# esquema.net
KiCad netlist of a schematic drawn in EAGLE
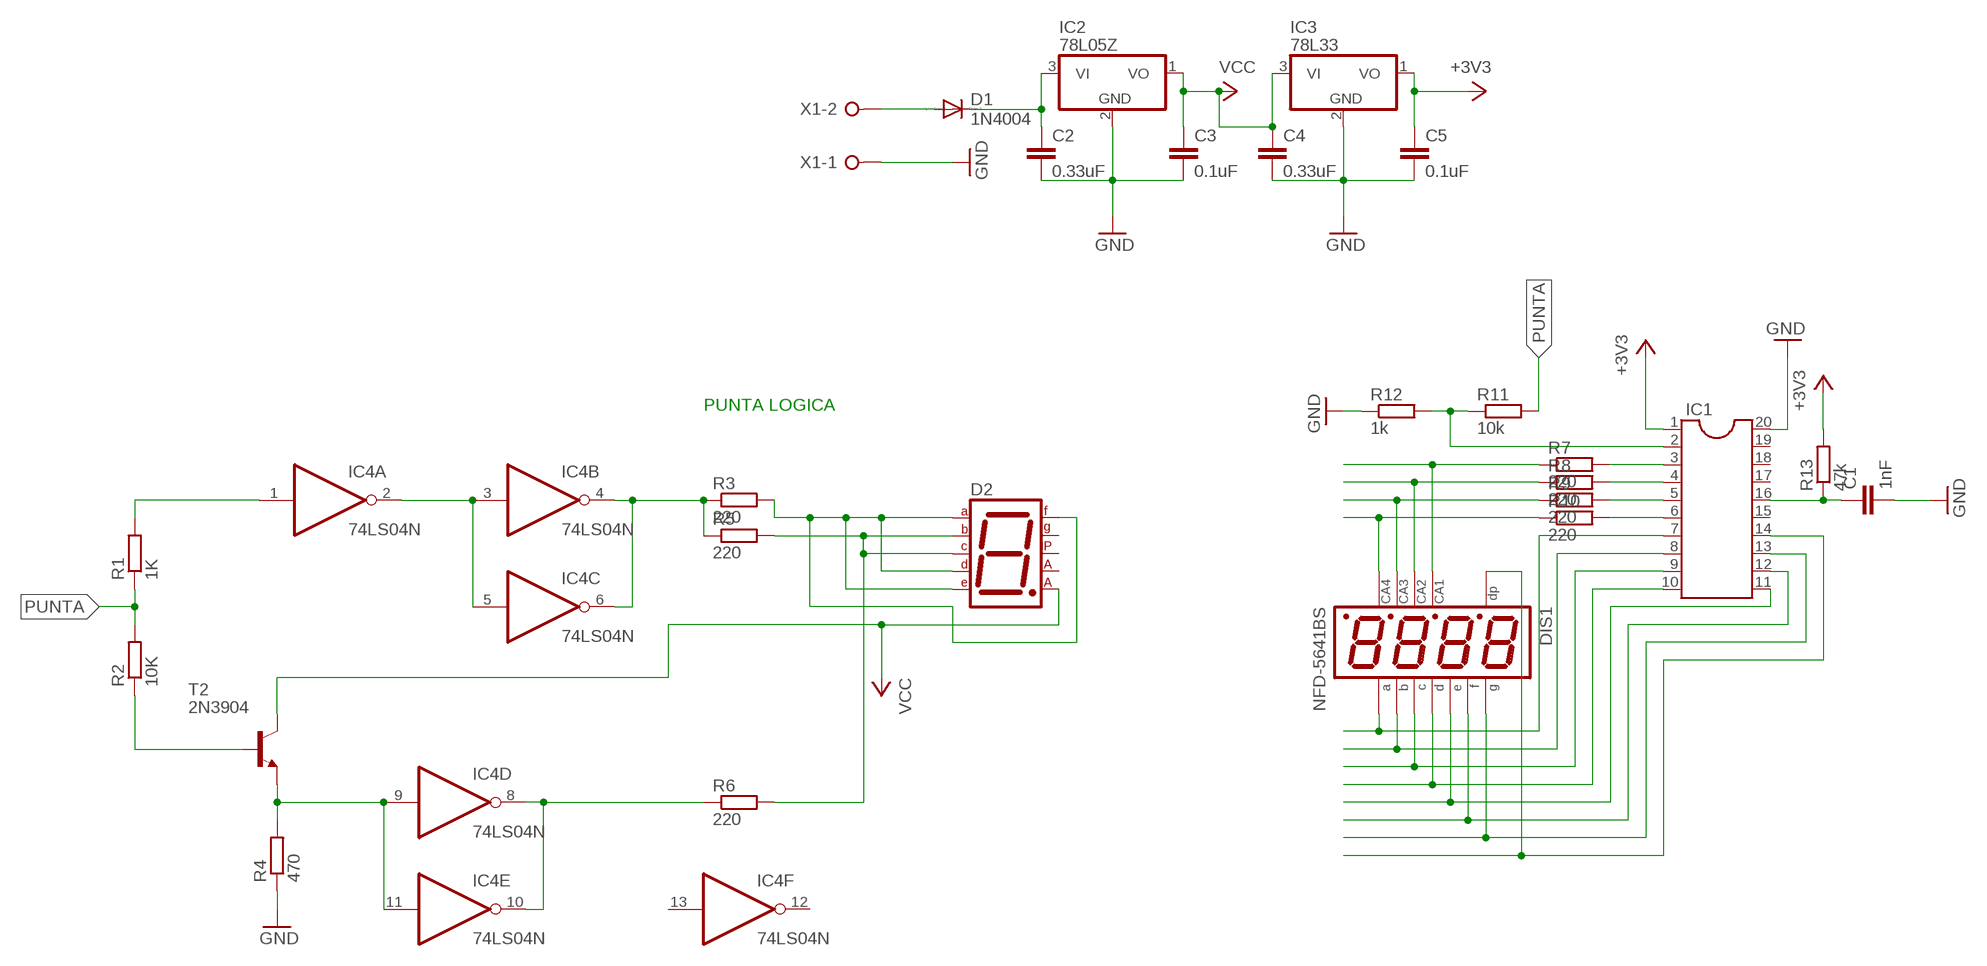
[diagram p0: schematic, sheet 1]

(export (version "E")
  (design (tool "Eeschema 10.0.6"))
  (components
    (comp (ref "C1")
      (value "1nF")
      (footprint "eagle-import:C050-024X044")
      (libsource (lib "eagle-import") (part "C-EU050-024X044"))
    )
    (comp (ref "C2")
      (value "0.33uF")
      (footprint "eagle-import:C050-024X044")
      (libsource (lib "eagle-import") (part "C-EU050-024X044"))
    )
    (comp (ref "C3")
      (value "0.1uF")
      (footprint "eagle-import:C050-024X044")
      (libsource (lib "eagle-import") (part "C-EU050-024X044"))
    )
    (comp (ref "C4")
      (value "0.33uF")
      (footprint "eagle-import:C050-024X044")
      (libsource (lib "eagle-import") (part "C-EU050-024X044"))
    )
    (comp (ref "C5")
      (value "0.1uF")
      (footprint "eagle-import:C050-024X044")
      (libsource (lib "eagle-import") (part "C-EU050-024X044"))
    )
    (comp (ref "D1")
      (value "1N4004")
      (footprint "eagle-import:DO41-10")
      (libsource (lib "eagle-import") (part "1N4004"))
    )
    (comp (ref "D2")
      (value "7SEG-CA")
      (footprint "eagle-import:7SEG-13")
      (libsource (lib "eagle-import") (part "7SEG-CA"))
    )
    (comp (ref "DIS1")
      (value "NFD-5641BS")
      (footprint "eagle-import:NFD-5641")
      (libsource (lib "eagle-import") (part "NFD-5641BS"))
    )
    (comp (ref "IC1")
      (value "DIL20S")
      (footprint "eagle-import:SOCKET-20")
      (libsource (lib "eagle-import") (part "DIL20S"))
    )
    (comp (ref "IC2")
      (value "78L05Z")
      (footprint "eagle-import:TO92")
      (libsource (lib "eagle-import") (part "78ZL05"))
    )
    (comp (ref "IC3")
      (value "78L33")
      (footprint "eagle-import:TO92")
      (libsource (lib "eagle-import") (part "78ZL05"))
    )
    (comp (ref "IC4")
      (value "74LS04N")
      (footprint "eagle-import:DIL14")
      (libsource (lib "eagle-import") (part "7404NLS"))
    )
    (comp (ref "R1")
      (value "1K")
      (footprint "eagle-import:0207_7")
      (libsource (lib "eagle-import") (part "R-EU_0207/7"))
    )
    (comp (ref "R2")
      (value "10K")
      (footprint "eagle-import:0207_7")
      (libsource (lib "eagle-import") (part "R-EU_0207/7"))
    )
    (comp (ref "R3")
      (value "220")
      (footprint "eagle-import:0207_7")
      (libsource (lib "eagle-import") (part "R-EU_0207/7"))
    )
    (comp (ref "R4")
      (value "470")
      (footprint "eagle-import:0207_7")
      (libsource (lib "eagle-import") (part "R-EU_0207/7"))
    )
    (comp (ref "R5")
      (value "220")
      (footprint "eagle-import:0207_7")
      (libsource (lib "eagle-import") (part "R-EU_0207/7"))
    )
    (comp (ref "R6")
      (value "220")
      (footprint "eagle-import:0207_7")
      (libsource (lib "eagle-import") (part "R-EU_0207/7"))
    )
    (comp (ref "R7")
      (value "220")
      (footprint "eagle-import:0207_7")
      (libsource (lib "eagle-import") (part "R-EU_0207/7"))
    )
    (comp (ref "R8")
      (value "220")
      (footprint "eagle-import:0207_7")
      (libsource (lib "eagle-import") (part "R-EU_0207/7"))
    )
    (comp (ref "R9")
      (value "220")
      (footprint "eagle-import:0207_7")
      (libsource (lib "eagle-import") (part "R-EU_0207/7"))
    )
    (comp (ref "R10")
      (value "220")
      (footprint "eagle-import:0207_7")
      (libsource (lib "eagle-import") (part "R-EU_0207/7"))
    )
    (comp (ref "R11")
      (value "10k")
      (footprint "eagle-import:0207_7")
      (libsource (lib "eagle-import") (part "R-EU_0207/7"))
    )
    (comp (ref "R12")
      (value "1k")
      (footprint "eagle-import:0207_7")
      (libsource (lib "eagle-import") (part "R-EU_0207/7"))
    )
    (comp (ref "R13")
      (value "47k")
      (footprint "eagle-import:0207_7")
      (libsource (lib "eagle-import") (part "R-EU_0207/7"))
    )
    (comp (ref "T2")
      (value "2N3904")
      (footprint "eagle-import:TO92")
      (libsource (lib "eagle-import") (part "2N3904"))
    )
    (comp (ref "X1")
      (value "W237-02P")
      (footprint "eagle-import:W237-132")
      (libsource (lib "eagle-import") (part "W237-02P"))
    )
  )
  (nets
    (net (code "1") (name "+3V3") (class "Default")
      (node (ref "C5") (pin "1") (pinfunction "1_1") (pintype "passive"))
      (node (ref "IC1") (pin "1") (pinfunction "1_1") (pintype "passive"))
      (node (ref "IC3") (pin "1") (pinfunction "VO_1") (pintype "passive"))
      (node (ref "R13") (pin "2") (pinfunction "2_2") (pintype "passive"))
    )
    (net (code "2") (name "GND") (class "Default")
      (node (ref "C1") (pin "2") (pinfunction "2_2") (pintype "passive"))
      (node (ref "C2") (pin "2") (pinfunction "2_2") (pintype "passive"))
      (node (ref "C3") (pin "2") (pinfunction "2_2") (pintype "passive"))
      (node (ref "C4") (pin "2") (pinfunction "2_2") (pintype "passive"))
      (node (ref "C5") (pin "2") (pinfunction "2_2") (pintype "passive"))
      (node (ref "IC1") (pin "20") (pinfunction "20_20") (pintype "passive"))
      (node (ref "IC2") (pin "2") (pinfunction "GND_2") (pintype "passive"))
      (node (ref "IC3") (pin "2") (pinfunction "GND_2") (pintype "passive"))
      (node (ref "R12") (pin "1") (pinfunction "1_1") (pintype "passive"))
      (node (ref "R4") (pin "1") (pinfunction "1_1") (pintype "passive"))
      (node (ref "X1") (pin "1") (pinfunction "KL_1") (pintype "passive"))
    )
    (net (code "3") (name "Net-(C1-Pad1)") (class "Default")
      (node (ref "C1") (pin "1") (pinfunction "1_1") (pintype "passive"))
      (node (ref "IC1") (pin "16") (pinfunction "16_16") (pintype "passive"))
      (node (ref "R13") (pin "1") (pinfunction "1_1") (pintype "passive"))
    )
    (net (code "4") (name "Net-(D2-A)") (class "Default")
      (node (ref "D2") (pin "1") (pinfunction "E_1") (pintype "passive"))
      (node (ref "D2") (pin "2") (pinfunction "D_2") (pintype "passive"))
      (node (ref "D2") (pin "7") (pinfunction "A_7") (pintype "passive"))
      (node (ref "D2") (pin "9") (pinfunction "F_9") (pintype "passive"))
      (node (ref "R3") (pin "2") (pinfunction "2_2") (pintype "passive"))
    )
    (net (code "5") (name "Net-(D2-B)") (class "Default")
      (node (ref "D2") (pin "4") (pinfunction "C_4") (pintype "passive"))
      (node (ref "D2") (pin "6") (pinfunction "B_6") (pintype "passive"))
      (node (ref "R5") (pin "2") (pinfunction "2_2") (pintype "passive"))
      (node (ref "R6") (pin "2") (pinfunction "2_2") (pintype "passive"))
    )
    (net (code "6") (name "Net-(DIS1-PadP$1)") (class "Default")
      (node (ref "DIS1") (pin "P$1") (pinfunction "P$1_P$1") (pintype "bidirectional"))
      (node (ref "IC1") (pin "11") (pinfunction "11_11") (pintype "passive"))
    )
    (net (code "7") (name "Net-(DIS1-PadP$2)") (class "Default")
      (node (ref "DIS1") (pin "P$2") (pinfunction "P$2_P$2") (pintype "bidirectional"))
      (node (ref "IC1") (pin "10") (pinfunction "10_10") (pintype "passive"))
    )
    (net (code "8") (name "Net-(DIS1-PadP$3)") (class "Default")
      (node (ref "DIS1") (pin "P$3") (pinfunction "P$3_P$3") (pintype "bidirectional"))
      (node (ref "IC1") (pin "14") (pinfunction "14_14") (pintype "passive"))
    )
    (net (code "9") (name "Net-(DIS1-PadP$4)") (class "Default")
      (node (ref "DIS1") (pin "P$4") (pinfunction "P$4_P$4") (pintype "bidirectional"))
      (node (ref "IC1") (pin "9") (pinfunction "9_9") (pintype "passive"))
    )
    (net (code "10") (name "Net-(DIS1-PadP$5)") (class "Default")
      (node (ref "DIS1") (pin "P$5") (pinfunction "P$5_P$5") (pintype "bidirectional"))
      (node (ref "IC1") (pin "13") (pinfunction "13_13") (pintype "passive"))
    )
    (net (code "11") (name "Net-(DIS1-PadP$6)") (class "Default")
      (node (ref "DIS1") (pin "P$6") (pinfunction "P$6_P$6") (pintype "bidirectional"))
      (node (ref "R10") (pin "1") (pinfunction "1_1") (pintype "passive"))
    )
    (net (code "12") (name "Net-(DIS1-PadP$7)") (class "Default")
      (node (ref "DIS1") (pin "P$7") (pinfunction "P$7_P$7") (pintype "bidirectional"))
      (node (ref "IC1") (pin "8") (pinfunction "8_8") (pintype "passive"))
    )
    (net (code "13") (name "Net-(DIS1-PadP$8)") (class "Default")
      (node (ref "DIS1") (pin "P$8") (pinfunction "P$8_P$8") (pintype "bidirectional"))
      (node (ref "R9") (pin "1") (pinfunction "1_1") (pintype "passive"))
    )
    (net (code "14") (name "Net-(DIS1-PadP$9)") (class "Default")
      (node (ref "DIS1") (pin "P$9") (pinfunction "P$9_P$9") (pintype "bidirectional"))
      (node (ref "R8") (pin "1") (pinfunction "1_1") (pintype "passive"))
    )
    (net (code "15") (name "Net-(DIS1-PadP$10)") (class "Default")
      (node (ref "DIS1") (pin "P$10") (pinfunction "P$10_P$10") (pintype "bidirectional"))
      (node (ref "IC1") (pin "12") (pinfunction "12_12") (pintype "passive"))
    )
    (net (code "16") (name "Net-(DIS1-PadP$11)") (class "Default")
      (node (ref "DIS1") (pin "P$11") (pinfunction "P$11_P$11") (pintype "bidirectional"))
      (node (ref "IC1") (pin "7") (pinfunction "7_7") (pintype "passive"))
    )
    (net (code "17") (name "Net-(DIS1-PadP$12)") (class "Default")
      (node (ref "DIS1") (pin "P$12") (pinfunction "P$12_P$12") (pintype "bidirectional"))
      (node (ref "R7") (pin "1") (pinfunction "1_1") (pintype "passive"))
    )
    (net (code "18") (name "Net-(IC1-Pad2)") (class "Default")
      (node (ref "IC1") (pin "2") (pinfunction "2_2") (pintype "passive"))
      (node (ref "R11") (pin "1") (pinfunction "1_1") (pintype "passive"))
      (node (ref "R12") (pin "2") (pinfunction "2_2") (pintype "passive"))
    )
    (net (code "19") (name "Net-(IC1-Pad3)") (class "Default")
      (node (ref "IC1") (pin "3") (pinfunction "3_3") (pintype "passive"))
      (node (ref "R7") (pin "2") (pinfunction "2_2") (pintype "passive"))
    )
    (net (code "20") (name "Net-(IC1-Pad4)") (class "Default")
      (node (ref "IC1") (pin "4") (pinfunction "4_4") (pintype "passive"))
      (node (ref "R8") (pin "2") (pinfunction "2_2") (pintype "passive"))
    )
    (net (code "21") (name "Net-(IC1-Pad5)") (class "Default")
      (node (ref "IC1") (pin "5") (pinfunction "5_5") (pintype "passive"))
      (node (ref "R9") (pin "2") (pinfunction "2_2") (pintype "passive"))
    )
    (net (code "22") (name "Net-(IC1-Pad6)") (class "Default")
      (node (ref "IC1") (pin "6") (pinfunction "6_6") (pintype "passive"))
      (node (ref "R10") (pin "2") (pinfunction "2_2") (pintype "passive"))
    )
    (net (code "23") (name "Net-(IC2-VI)") (class "Default")
      (node (ref "C2") (pin "1") (pinfunction "1_1") (pintype "passive"))
      (node (ref "D1") (pin "C") (pinfunction "C_C") (pintype "passive"))
      (node (ref "IC2") (pin "3") (pinfunction "VI_3") (pintype "input"))
    )
    (net (code "24") (name "Net-(IC4A-I)") (class "Default")
      (node (ref "IC4") (pin "1") (pinfunction "I_1") (pintype "input"))
      (node (ref "R1") (pin "2") (pinfunction "2_2") (pintype "passive"))
    )
    (net (code "25") (name "Net-(IC4A-O)") (class "Default")
      (node (ref "IC4") (pin "2") (pinfunction "O_2") (pintype "output"))
      (node (ref "IC4") (pin "3") (pinfunction "I_3") (pintype "input"))
      (node (ref "IC4") (pin "5") (pinfunction "I_5") (pintype "input"))
    )
    (net (code "26") (name "Net-(IC4B-O)") (class "Default")
      (node (ref "IC4") (pin "4") (pinfunction "O_4") (pintype "output"))
      (node (ref "IC4") (pin "6") (pinfunction "O_6") (pintype "output"))
      (node (ref "R3") (pin "1") (pinfunction "1_1") (pintype "passive"))
      (node (ref "R5") (pin "1") (pinfunction "1_1") (pintype "passive"))
    )
    (net (code "27") (name "Net-(IC4D-I)") (class "Default")
      (node (ref "IC4") (pin "11") (pinfunction "I_11") (pintype "input"))
      (node (ref "IC4") (pin "9") (pinfunction "I_9") (pintype "input"))
      (node (ref "R4") (pin "2") (pinfunction "2_2") (pintype "passive"))
      (node (ref "T2") (pin "3") (pinfunction "E_3") (pintype "passive"))
    )
    (net (code "28") (name "Net-(IC4D-O)") (class "Default")
      (node (ref "IC4") (pin "10") (pinfunction "O_10") (pintype "output"))
      (node (ref "IC4") (pin "8") (pinfunction "O_8") (pintype "output"))
      (node (ref "R6") (pin "1") (pinfunction "1_1") (pintype "passive"))
    )
    (net (code "29") (name "Net-(T2-B)") (class "Default")
      (node (ref "R2") (pin "1") (pinfunction "1_1") (pintype "passive"))
      (node (ref "T2") (pin "2") (pinfunction "B_2") (pintype "passive"))
    )
    (net (code "30") (name "Net-(X1B-KL)") (class "Default")
      (node (ref "D1") (pin "A") (pinfunction "A_A") (pintype "passive"))
      (node (ref "X1") (pin "2") (pinfunction "KL_2") (pintype "passive"))
    )
    (net (code "31") (name "PUNTA") (class "Default")
      (node (ref "R1") (pin "1") (pinfunction "1_1") (pintype "passive"))
      (node (ref "R11") (pin "2") (pinfunction "2_2") (pintype "passive"))
      (node (ref "R2") (pin "2") (pinfunction "2_2") (pintype "passive"))
    )
    (net (code "32") (name "VCC") (class "Default")
      (node (ref "C3") (pin "1") (pinfunction "1_1") (pintype "passive"))
      (node (ref "C4") (pin "1") (pinfunction "1_1") (pintype "passive"))
      (node (ref "D2") (pin "8") (pinfunction "CA2_8") (pintype "passive"))
      (node (ref "IC2") (pin "1") (pinfunction "VO_1") (pintype "passive"))
      (node (ref "IC3") (pin "3") (pinfunction "VI_3") (pintype "input"))
      (node (ref "T2") (pin "1") (pinfunction "C_1") (pintype "passive"))
    )
    (net (code "33") (name "unconnected-(D2-CA1-Pad3)") (class "Default")
      (node (ref "D2") (pin "3") (pinfunction "CA1_3") (pintype "passive"))
    )
    (net (code "34") (name "unconnected-(D2-DP-Pad5)") (class "Default")
      (node (ref "D2") (pin "5") (pinfunction "DP_5") (pintype "passive"))
    )
    (net (code "35") (name "unconnected-(D2-G-Pad10)") (class "Default")
      (node (ref "D2") (pin "10") (pinfunction "G_10") (pintype "passive"))
    )
    (net (code "36") (name "unconnected-(IC1-Pad15)") (class "Default")
      (node (ref "IC1") (pin "15") (pinfunction "15_15") (pintype "passive"))
    )
    (net (code "37") (name "unconnected-(IC1-Pad17)") (class "Default")
      (node (ref "IC1") (pin "17") (pinfunction "17_17") (pintype "passive"))
    )
    (net (code "38") (name "unconnected-(IC1-Pad18)") (class "Default")
      (node (ref "IC1") (pin "18") (pinfunction "18_18") (pintype "passive"))
    )
    (net (code "39") (name "unconnected-(IC1-Pad19)") (class "Default")
      (node (ref "IC1") (pin "19") (pinfunction "19_19") (pintype "passive"))
    )
    (net (code "40") (name "unconnected-(IC4F-I-Pad13)") (class "Default")
      (node (ref "IC4") (pin "13") (pinfunction "I_13") (pintype "input"))
    )
    (net (code "41") (name "unconnected-(IC4F-O-Pad12)") (class "Default")
      (node (ref "IC4") (pin "12") (pinfunction "O_12") (pintype "output"))
    )
  )
)
